# HDC100X-Breakout_v11.net
KiCad netlist of a schematic drawn in EAGLE
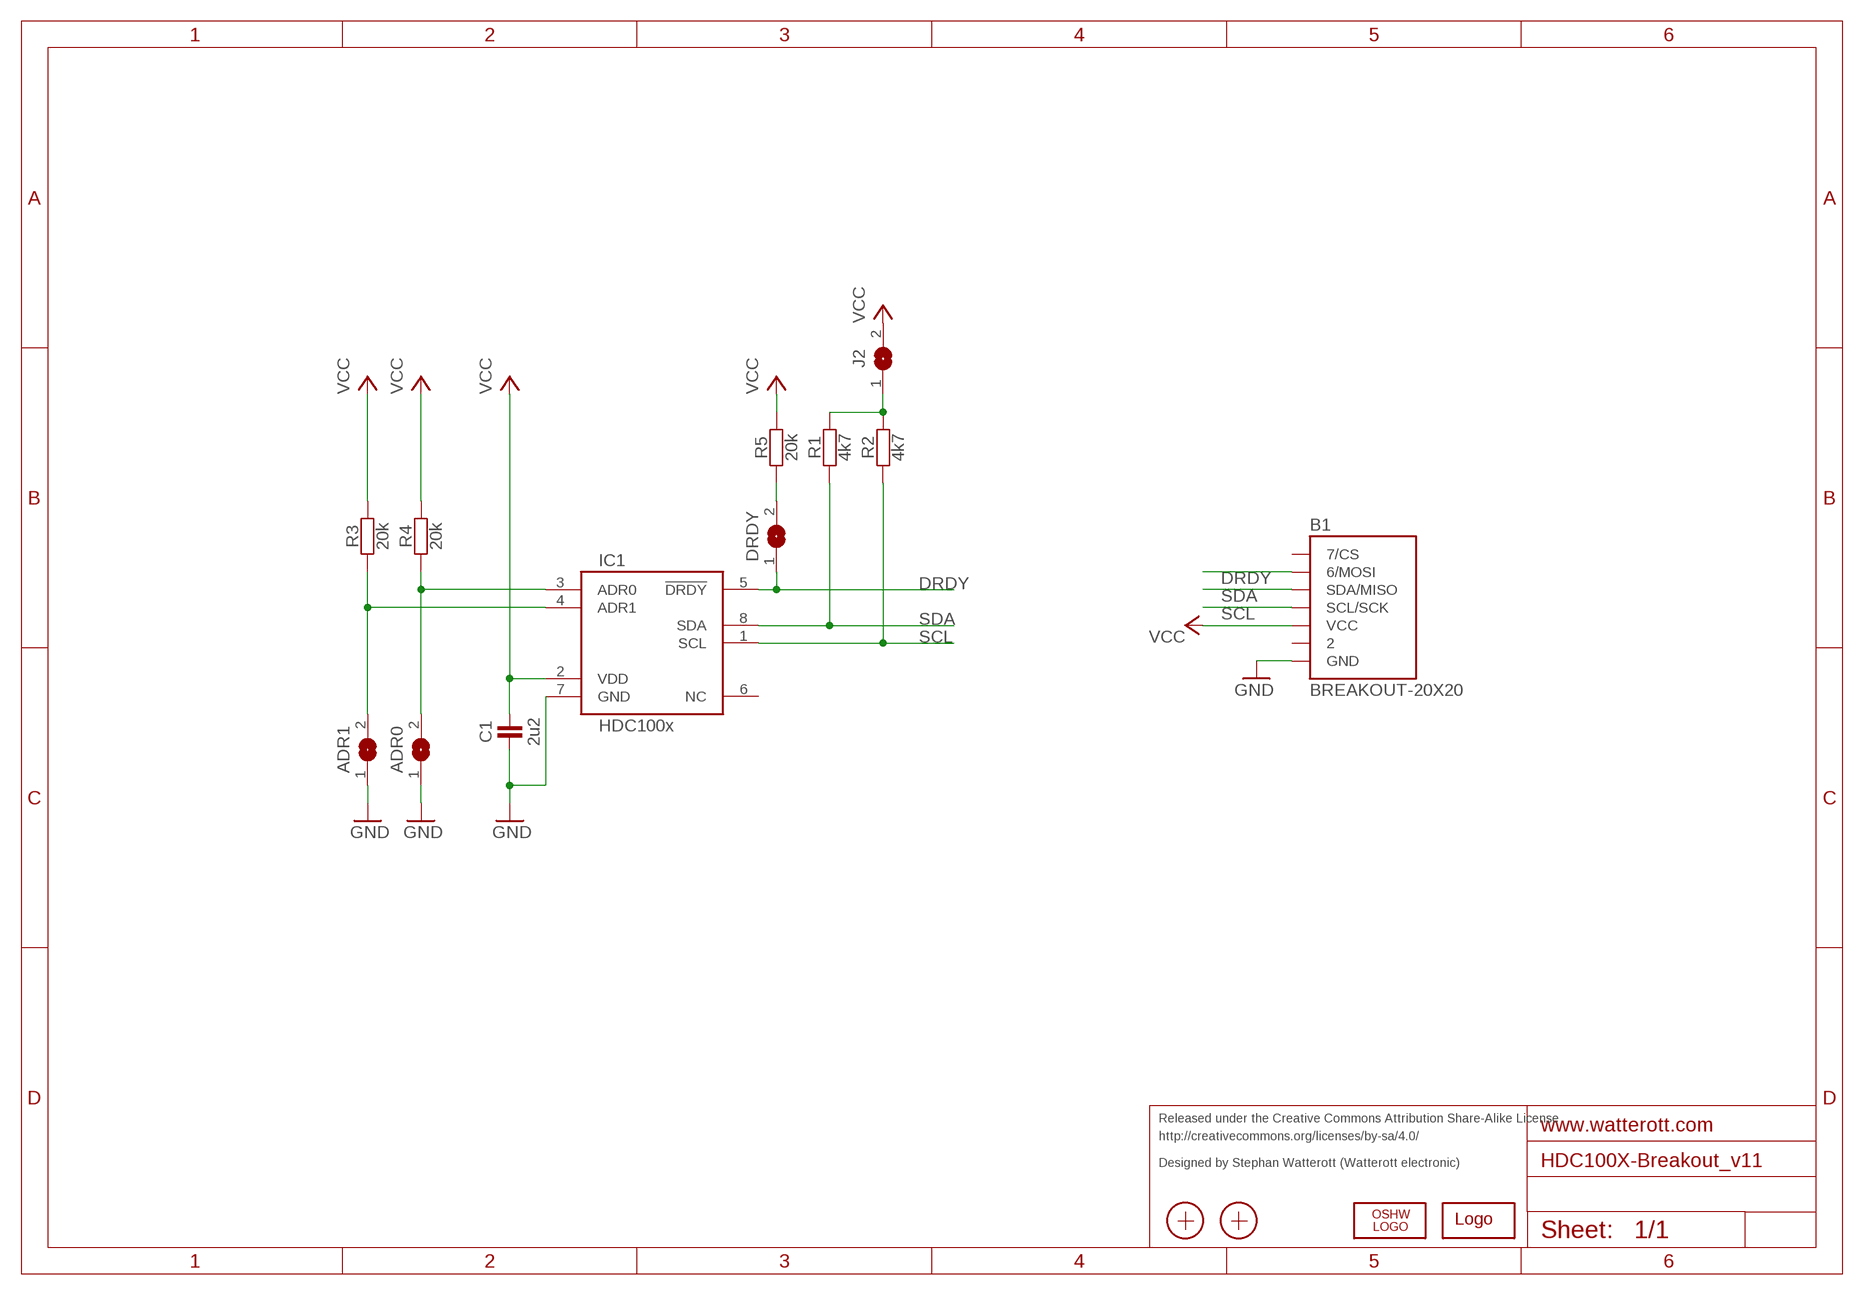
[diagram p0: schematic, sheet 1]

(export (version "E")
  (design (tool "Eeschema 10.0.6"))
  (components
    (comp (ref "ADR0")
      (value "JUMPER2-0402")
      (footprint "eagle-import:JUMPER2-0402")
      (libsource (lib "eagle-import") (part "JUMPER2-0402"))
    )
    (comp (ref "ADR1")
      (value "JUMPER2-0402")
      (footprint "eagle-import:JUMPER2-0402")
      (libsource (lib "eagle-import") (part "JUMPER2-0402"))
    )
    (comp (ref "B1")
      (value "BREAKOUT-20X20")
      (footprint "eagle-import:BREAKOUT-20X20")
      (libsource (lib "eagle-import") (part "BREAKOUT-20X20"))
    )
    (comp (ref "C1")
      (value "2u2")
      (footprint "eagle-import:R0402")
      (libsource (lib "eagle-import") (part "CAPACITOR-C0402"))
    )
    (comp (ref "DRDY")
      (value "JUMPER2-0402")
      (footprint "eagle-import:JUMPER2-0402")
      (libsource (lib "eagle-import") (part "JUMPER2-0402"))
    )
    (comp (ref "IC1")
      (value "HDC100x")
      (footprint "eagle-import:WLCSP")
      (libsource (lib "eagle-import") (part "HDC1008"))
    )
    (comp (ref "J2")
      (value "JUMPER2-0603")
      (footprint "eagle-import:JUMPER2-0603")
      (libsource (lib "eagle-import") (part "JUMPER2-0603"))
    )
    (comp (ref "LOGO2")
      (value "OSHW_LOGOX0070")
      (footprint "eagle-import:OSHW_6X70")
      (libsource (lib "eagle-import") (part "OSHW_LOGOX0070"))
    )
    (comp (ref "LOGO3")
      (value "LOGO-S_PLACE_M")
      (footprint "eagle-import:SPARK_TPLACE_M")
      (libsource (lib "eagle-import") (part "LOGO-S_PLACE_M"))
    )
    (comp (ref "R1")
      (value "4k7")
      (footprint "eagle-import:R0402")
      (libsource (lib "eagle-import") (part "RESISTOR-R0402"))
    )
    (comp (ref "R2")
      (value "4k7")
      (footprint "eagle-import:R0402")
      (libsource (lib "eagle-import") (part "RESISTOR-R0402"))
    )
    (comp (ref "R3")
      (value "20k")
      (footprint "eagle-import:R0402")
      (libsource (lib "eagle-import") (part "RESISTOR-R0402"))
    )
    (comp (ref "R4")
      (value "20k")
      (footprint "eagle-import:R0402")
      (libsource (lib "eagle-import") (part "RESISTOR-R0402"))
    )
    (comp (ref "R5")
      (value "20k")
      (footprint "eagle-import:R0402")
      (libsource (lib "eagle-import") (part "RESISTOR-R0402"))
    )
    (comp (ref "X1")
      (value "PASSER-07")
      (footprint "eagle-import:PASSER_07MM")
      (libsource (lib "eagle-import") (part "PASSER-07"))
    )
    (comp (ref "X2")
      (value "PASSER-07")
      (footprint "eagle-import:PASSER_07MM")
      (libsource (lib "eagle-import") (part "PASSER-07"))
    )
  )
  (nets
    (net (code "1") (name "/DRDY") (class "Default")
      (node (ref "B1") (pin "MOSI") (pinfunction "6/MOSI_MOSI") (pintype "bidirectional"))
      (node (ref "DRDY") (pin "1") (pinfunction "1_1") (pintype "passive"))
      (node (ref "IC1") (pin "5") (pinfunction "~{DRDY}_5") (pintype "output"))
    )
    (net (code "2") (name "/SCL") (class "Default")
      (node (ref "B1") (pin "SCL/SCK") (pinfunction "SCL/SCK_SCL/SCK") (pintype "bidirectional"))
      (node (ref "IC1") (pin "1") (pinfunction "SCL_1") (pintype "input"))
      (node (ref "R2") (pin "1") (pinfunction "1_1") (pintype "passive"))
    )
    (net (code "3") (name "/SDA") (class "Default")
      (node (ref "B1") (pin "SDA/MISO") (pinfunction "SDA/MISO_SDA/MISO") (pintype "bidirectional"))
      (node (ref "IC1") (pin "8") (pinfunction "SDA_8") (pintype "bidirectional"))
      (node (ref "R1") (pin "1") (pinfunction "1_1") (pintype "passive"))
    )
    (net (code "4") (name "GND") (class "Default")
      (node (ref "ADR0") (pin "1") (pinfunction "1_1") (pintype "passive"))
      (node (ref "ADR1") (pin "1") (pinfunction "1_1") (pintype "passive"))
      (node (ref "B1") (pin "GND") (pinfunction "GND_GND") (pintype "power_in"))
      (node (ref "C1") (pin "1") (pinfunction "1_1") (pintype "passive"))
      (node (ref "IC1") (pin "7") (pinfunction "GND_7") (pintype "power_in"))
    )
    (net (code "5") (name "Net-(DRDY-Pad2)") (class "Default")
      (node (ref "DRDY") (pin "2") (pinfunction "2_2") (pintype "passive"))
      (node (ref "R5") (pin "1") (pinfunction "1_1") (pintype "passive"))
    )
    (net (code "6") (name "Net-(IC1-ADR0)") (class "Default")
      (node (ref "ADR0") (pin "2") (pinfunction "2_2") (pintype "passive"))
      (node (ref "IC1") (pin "3") (pinfunction "ADR0_3") (pintype "input"))
      (node (ref "R4") (pin "1") (pinfunction "1_1") (pintype "passive"))
    )
    (net (code "7") (name "Net-(IC1-ADR1)") (class "Default")
      (node (ref "ADR1") (pin "2") (pinfunction "2_2") (pintype "passive"))
      (node (ref "IC1") (pin "4") (pinfunction "ADR1_4") (pintype "input"))
      (node (ref "R3") (pin "1") (pinfunction "1_1") (pintype "passive"))
    )
    (net (code "8") (name "Net-(J2-Pad1)") (class "Default")
      (node (ref "J2") (pin "1") (pinfunction "1_1") (pintype "passive"))
      (node (ref "R1") (pin "2") (pinfunction "2_2") (pintype "passive"))
      (node (ref "R2") (pin "2") (pinfunction "2_2") (pintype "passive"))
    )
    (net (code "9") (name "VCC") (class "Default")
      (node (ref "B1") (pin "VCC") (pinfunction "VCC_VCC") (pintype "power_in"))
      (node (ref "C1") (pin "2") (pinfunction "2_2") (pintype "passive"))
      (node (ref "IC1") (pin "2") (pinfunction "VDD_2") (pintype "power_in"))
      (node (ref "J2") (pin "2") (pinfunction "2_2") (pintype "passive"))
      (node (ref "R3") (pin "2") (pinfunction "2_2") (pintype "passive"))
      (node (ref "R4") (pin "2") (pinfunction "2_2") (pintype "passive"))
      (node (ref "R5") (pin "2") (pinfunction "2_2") (pintype "passive"))
    )
    (net (code "10") (name "unconnected-(B1-7{slash}CS-PadCS)") (class "Default")
      (node (ref "B1") (pin "CS") (pinfunction "7/CS_CS") (pintype "bidirectional"))
    )
    (net (code "11") (name "unconnected-(B1-Pad2)") (class "Default")
      (node (ref "B1") (pin "2") (pinfunction "2_2") (pintype "bidirectional"))
    )
    (net (code "12") (name "unconnected-(IC1-NC-Pad6)") (class "Default")
      (node (ref "IC1") (pin "6") (pinfunction "NC_6") (pintype "no_connect"))
    )
  )
)
